# String_Shooter.net
KiCad netlist of a schematic drawn in EAGLE
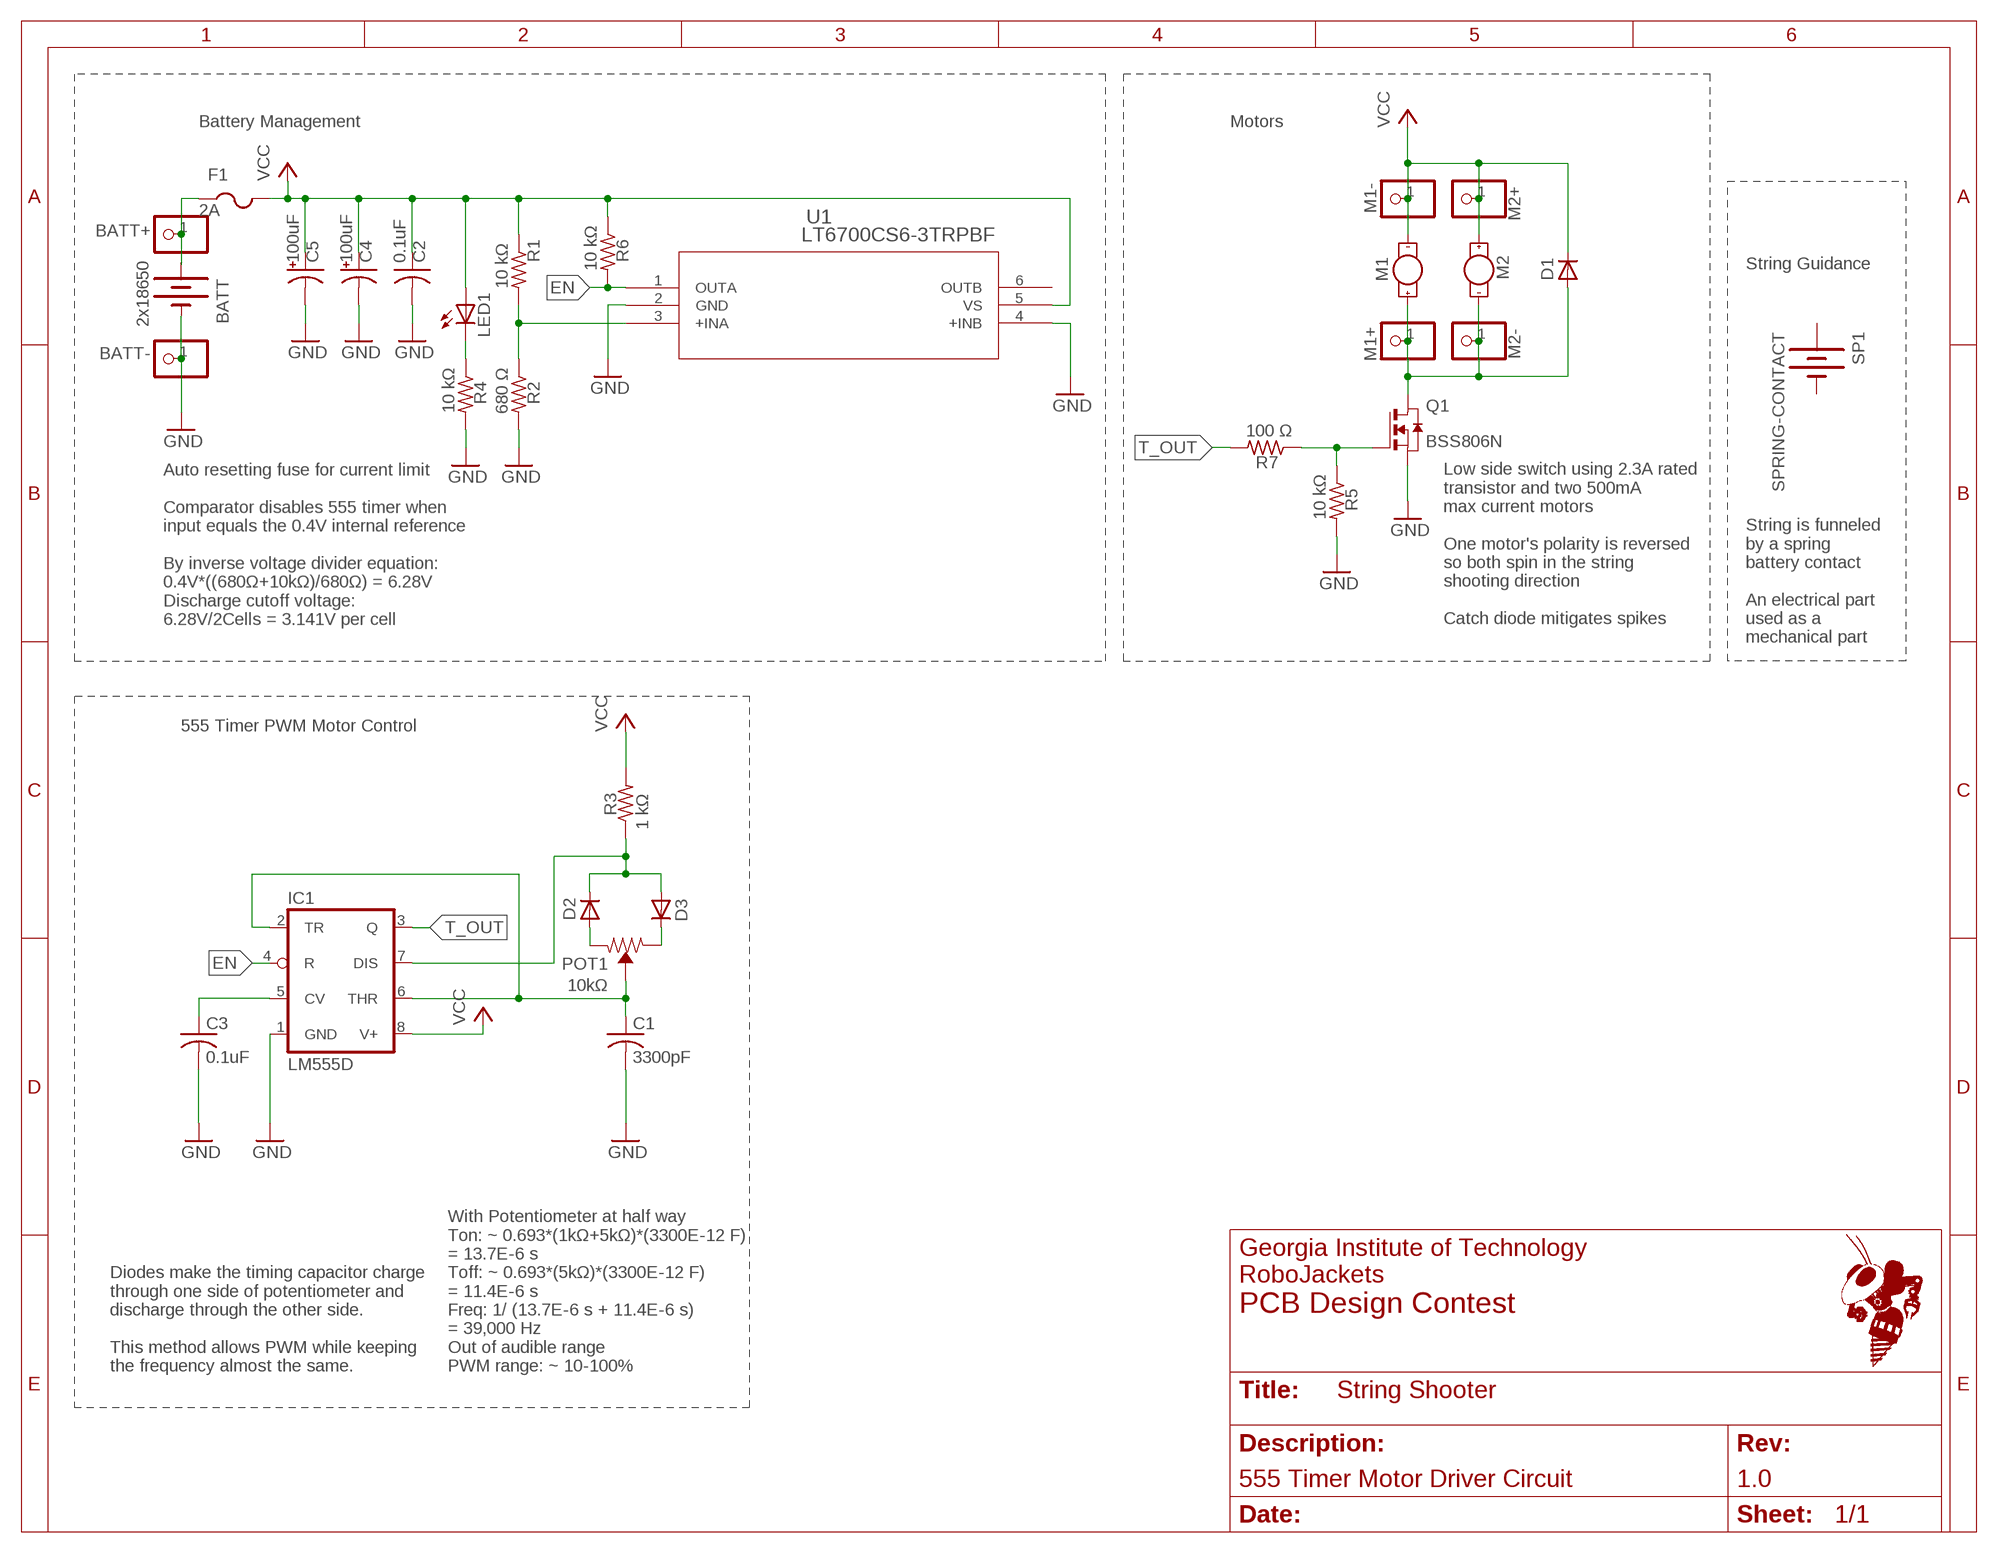
[diagram p0: schematic, sheet 1]

(export (version "E")
  (design (tool "Eeschema 10.0.6"))
  (components
    (comp (ref "BATT")
      (value "2x18650")
      (footprint "eagle-import:BATTERY-CASE")
      (libsource (lib "eagle-import") (part "BATTERY-DEVICE"))
    )
    (comp (ref "BATT+")
      (value "PINHD-1X1CB")
      (footprint "eagle-import:1X01-CLEANBIG")
      (libsource (lib "eagle-import") (part "PINHD-1X1CB"))
    )
    (comp (ref "BATT-")
      (value "PINHD-1X1CB")
      (footprint "eagle-import:1X01-CLEANBIG")
      (libsource (lib "eagle-import") (part "PINHD-1X1CB"))
    )
    (comp (ref "C1")
      (value "3300pF")
      (footprint "eagle-import:C0603")
      (libsource (lib "eagle-import") (part "C-USC0603"))
    )
    (comp (ref "C2")
      (value "0.1uF")
      (footprint "eagle-import:C0603")
      (libsource (lib "eagle-import") (part "C-USC0603"))
    )
    (comp (ref "C3")
      (value "0.1uF")
      (footprint "eagle-import:C0603")
      (libsource (lib "eagle-import") (part "C-USC0603"))
    )
    (comp (ref "C4")
      (value "100uF")
      (footprint "eagle-import:E22-6")
      (libsource (lib "eagle-import") (part "CPOL-USE22-6AXIAL"))
    )
    (comp (ref "C5")
      (value "100uF")
      (footprint "eagle-import:E22-6")
      (libsource (lib "eagle-import") (part "CPOL-USE22-6AXIAL"))
    )
    (comp (ref "D1")
      (value "DIODE-DO-214AC")
      (footprint "eagle-import:DO-214AC")
      (libsource (lib "eagle-import") (part "DIODE-DO-214AC"))
    )
    (comp (ref "D2")
      (value "DIODE-DO-214AC")
      (footprint "eagle-import:DO-214AC")
      (libsource (lib "eagle-import") (part "DIODE-DO-214AC"))
    )
    (comp (ref "D3")
      (value "DIODE-DO-214AC")
      (footprint "eagle-import:DO-214AC")
      (libsource (lib "eagle-import") (part "DIODE-DO-214AC"))
    )
    (comp (ref "F1")
      (value "2A")
      (footprint "eagle-import:R1206")
      (libsource (lib "eagle-import") (part "PTCFUSE-1206"))
    )
    (comp (ref "IC1")
      (value "LM555D")
      (footprint "eagle-import:SO08")
      (libsource (lib "eagle-import") (part "555DLM"))
    )
    (comp (ref "LED1")
      (value "LEDCHIP-LED0603")
      (footprint "eagle-import:CHIP-LED0603")
      (libsource (lib "eagle-import") (part "LEDCHIP-LED0603"))
    )
    (comp (ref "M1")
      (value "LITTLE-MOTOR")
      (footprint "eagle-import:DC_MOTOR")
      (libsource (lib "eagle-import") (part "LITTLE-MOTOR"))
    )
    (comp (ref "M1+")
      (value "PINHD-1X1CB")
      (footprint "eagle-import:1X01-CLEANBIG")
      (libsource (lib "eagle-import") (part "PINHD-1X1CB"))
    )
    (comp (ref "M1-")
      (value "PINHD-1X1CB")
      (footprint "eagle-import:1X01-CLEANBIG")
      (libsource (lib "eagle-import") (part "PINHD-1X1CB"))
    )
    (comp (ref "M2")
      (value "LITTLE-MOTOR")
      (footprint "eagle-import:DC_MOTOR")
      (libsource (lib "eagle-import") (part "LITTLE-MOTOR"))
    )
    (comp (ref "M2+")
      (value "PINHD-1X1CB")
      (footprint "eagle-import:1X01-CLEANBIG")
      (libsource (lib "eagle-import") (part "PINHD-1X1CB"))
    )
    (comp (ref "M2-")
      (value "PINHD-1X1CB")
      (footprint "eagle-import:1X01-CLEANBIG")
      (libsource (lib "eagle-import") (part "PINHD-1X1CB"))
    )
    (comp (ref "POT1")
      (value "10kΩ")
      (footprint "eagle-import:THUMBWHEEL-POT")
      (libsource (lib "eagle-import") (part "THUMBPOT"))
    )
    (comp (ref "Q1")
      (value "BSS806N")
      (footprint "eagle-import:SOT-23-3")
      (libsource (lib "eagle-import") (part "BSS806N"))
    )
    (comp (ref "R1")
      (value "10 kΩ")
      (footprint "eagle-import:R0603")
      (libsource (lib "eagle-import") (part "R-US_R0603"))
    )
    (comp (ref "R2")
      (value "680 Ω")
      (footprint "eagle-import:R0603")
      (libsource (lib "eagle-import") (part "R-US_R0603"))
    )
    (comp (ref "R3")
      (value "1 kΩ")
      (footprint "eagle-import:R0603")
      (libsource (lib "eagle-import") (part "R-US_R0603"))
    )
    (comp (ref "R4")
      (value "10 kΩ")
      (footprint "eagle-import:R0603")
      (libsource (lib "eagle-import") (part "R-US_R0603"))
    )
    (comp (ref "R5")
      (value "10 kΩ")
      (footprint "eagle-import:R0603")
      (libsource (lib "eagle-import") (part "R-US_R0603"))
    )
    (comp (ref "R6")
      (value "10 kΩ")
      (footprint "eagle-import:R0603")
      (libsource (lib "eagle-import") (part "R-US_R0603"))
    )
    (comp (ref "R7")
      (value "100 Ω")
      (footprint "eagle-import:R0603")
      (libsource (lib "eagle-import") (part "R-US_R0603"))
    )
    (comp (ref "SP1")
      (value "SPRING-CONTACT")
      (footprint "eagle-import:SPRING-CONTACT")
      (libsource (lib "eagle-import") (part "SPRING-CONTACT"))
    )
    (comp (ref "U1")
      (value "LT6700CS6-3TRPBF")
      (footprint "eagle-import:TSOT-23_S6")
      (fields
        (field (name "DIGI-KEY_PART_NUMBER") "LT6700CS6-3#TRPBFCT-ND")
        (field (name "MF") "Analog Devices")
        (field (name "MP") "LT6700CS6-3#TRPBF")
      )
      (libsource (lib "eagle-import") (part "LT6700CS6-3TRPBF"))
    )
  )
  (nets
    (net (code "1") (name "EN") (class "Default")
      (node (ref "IC1") (pin "4") (pinfunction "R_4") (pintype "input"))
      (node (ref "R6") (pin "2") (pinfunction "2_2") (pintype "passive"))
      (node (ref "U1") (pin "1") (pinfunction "OUTA_1") (pintype "output"))
    )
    (net (code "2") (name "GND") (class "Default")
      (node (ref "BATT-") (pin "1") (pinfunction "1_1") (pintype "passive"))
      (node (ref "C1") (pin "2") (pinfunction "2_2") (pintype "passive"))
      (node (ref "C2") (pin "2") (pinfunction "2_2") (pintype "passive"))
      (node (ref "C3") (pin "2") (pinfunction "2_2") (pintype "passive"))
      (node (ref "C4") (pin "-") (pinfunction "-_-") (pintype "passive"))
      (node (ref "C5") (pin "-") (pinfunction "-_-") (pintype "passive"))
      (node (ref "IC1") (pin "1") (pinfunction "GND_1") (pintype "power_in"))
      (node (ref "Q1") (pin "2") (pinfunction "S_2") (pintype "passive"))
      (node (ref "R2") (pin "2") (pinfunction "2_2") (pintype "passive"))
      (node (ref "R4") (pin "2") (pinfunction "2_2") (pintype "passive"))
      (node (ref "R5") (pin "2") (pinfunction "2_2") (pintype "passive"))
      (node (ref "U1") (pin "2") (pinfunction "GND_2") (pintype "power_in"))
      (node (ref "U1") (pin "4") (pinfunction "+INB_4") (pintype "input"))
    )
    (net (code "3") (name "Net-(BATT+-Pad1)") (class "Default")
      (node (ref "BATT+") (pin "1") (pinfunction "1_1") (pintype "passive"))
      (node (ref "F1") (pin "1") (pinfunction "1_1") (pintype "passive"))
    )
    (net (code "4") (name "Net-(IC1-CV)") (class "Default")
      (node (ref "C3") (pin "1") (pinfunction "1_1") (pintype "passive"))
      (node (ref "IC1") (pin "5") (pinfunction "CV_5") (pintype "input"))
    )
    (net (code "5") (name "Net-(IC1-DIS)") (class "Default")
      (node (ref "D2") (pin "C") (pinfunction "C_C") (pintype "passive"))
      (node (ref "D3") (pin "A") (pinfunction "A_A") (pintype "passive"))
      (node (ref "IC1") (pin "7") (pinfunction "DIS_7") (pintype "input"))
      (node (ref "R3") (pin "1") (pinfunction "1_1") (pintype "passive"))
    )
    (net (code "6") (name "Net-(IC1-THR)") (class "Default")
      (node (ref "C1") (pin "1") (pinfunction "1_1") (pintype "passive"))
      (node (ref "IC1") (pin "2") (pinfunction "TR_2") (pintype "input"))
      (node (ref "IC1") (pin "6") (pinfunction "THR_6") (pintype "input"))
      (node (ref "POT1") (pin "P$2") (pinfunction "WIPER_P$2") (pintype "passive"))
    )
    (net (code "7") (name "Net-(LED1-PadC)") (class "Default")
      (node (ref "LED1") (pin "C") (pinfunction "C_C") (pintype "passive"))
      (node (ref "R4") (pin "1") (pinfunction "1_1") (pintype "passive"))
    )
    (net (code "8") (name "Net-(POT1-CCW)") (class "Default")
      (node (ref "D2") (pin "A") (pinfunction "A_A") (pintype "passive"))
      (node (ref "POT1") (pin "P$1") (pinfunction "CCW_P$1") (pintype "passive"))
    )
    (net (code "9") (name "Net-(POT1-CW)") (class "Default")
      (node (ref "D3") (pin "C") (pinfunction "C_C") (pintype "passive"))
      (node (ref "POT1") (pin "P$3") (pinfunction "CW_P$3") (pintype "passive"))
    )
    (net (code "10") (name "Net-(Q1-D)") (class "Default")
      (node (ref "D1") (pin "A") (pinfunction "A_A") (pintype "passive"))
      (node (ref "M1+") (pin "1") (pinfunction "1_1") (pintype "passive"))
      (node (ref "M2-") (pin "1") (pinfunction "1_1") (pintype "passive"))
      (node (ref "Q1") (pin "3") (pinfunction "D_3") (pintype "passive"))
    )
    (net (code "11") (name "Net-(Q1-G)") (class "Default")
      (node (ref "Q1") (pin "1") (pinfunction "G_1") (pintype "passive"))
      (node (ref "R5") (pin "1") (pinfunction "1_1") (pintype "passive"))
      (node (ref "R7") (pin "1") (pinfunction "1_1") (pintype "passive"))
    )
    (net (code "12") (name "Net-(U1-+INA)") (class "Default")
      (node (ref "R1") (pin "2") (pinfunction "2_2") (pintype "passive"))
      (node (ref "R2") (pin "1") (pinfunction "1_1") (pintype "passive"))
      (node (ref "U1") (pin "3") (pinfunction "+INA_3") (pintype "input"))
    )
    (net (code "13") (name "T_OUT") (class "Default")
      (node (ref "IC1") (pin "3") (pinfunction "Q_3") (pintype "output"))
      (node (ref "R7") (pin "2") (pinfunction "2_2") (pintype "passive"))
    )
    (net (code "14") (name "VCC") (class "Default")
      (node (ref "C2") (pin "1") (pinfunction "1_1") (pintype "passive"))
      (node (ref "C4") (pin "+") (pinfunction "+_+") (pintype "passive"))
      (node (ref "C5") (pin "+") (pinfunction "+_+") (pintype "passive"))
      (node (ref "D1") (pin "C") (pinfunction "C_C") (pintype "passive"))
      (node (ref "F1") (pin "2") (pinfunction "2_2") (pintype "passive"))
      (node (ref "IC1") (pin "8") (pinfunction "V+_8") (pintype "power_in"))
      (node (ref "LED1") (pin "A") (pinfunction "A_A") (pintype "passive"))
      (node (ref "M1-") (pin "1") (pinfunction "1_1") (pintype "passive"))
      (node (ref "M2+") (pin "1") (pinfunction "1_1") (pintype "passive"))
      (node (ref "R1") (pin "1") (pinfunction "1_1") (pintype "passive"))
      (node (ref "R3") (pin "2") (pinfunction "2_2") (pintype "passive"))
      (node (ref "R6") (pin "1") (pinfunction "1_1") (pintype "passive"))
      (node (ref "U1") (pin "5") (pinfunction "VS_5") (pintype "power_in"))
    )
    (net (code "15") (name "unconnected-(U1-OUTB-Pad6)") (class "Default")
      (node (ref "U1") (pin "6") (pinfunction "OUTB_6") (pintype "output"))
    )
  )
)
